# BEP2_rev1_seeed_55x88.net
KiCad netlist of a schematic drawn in EAGLE
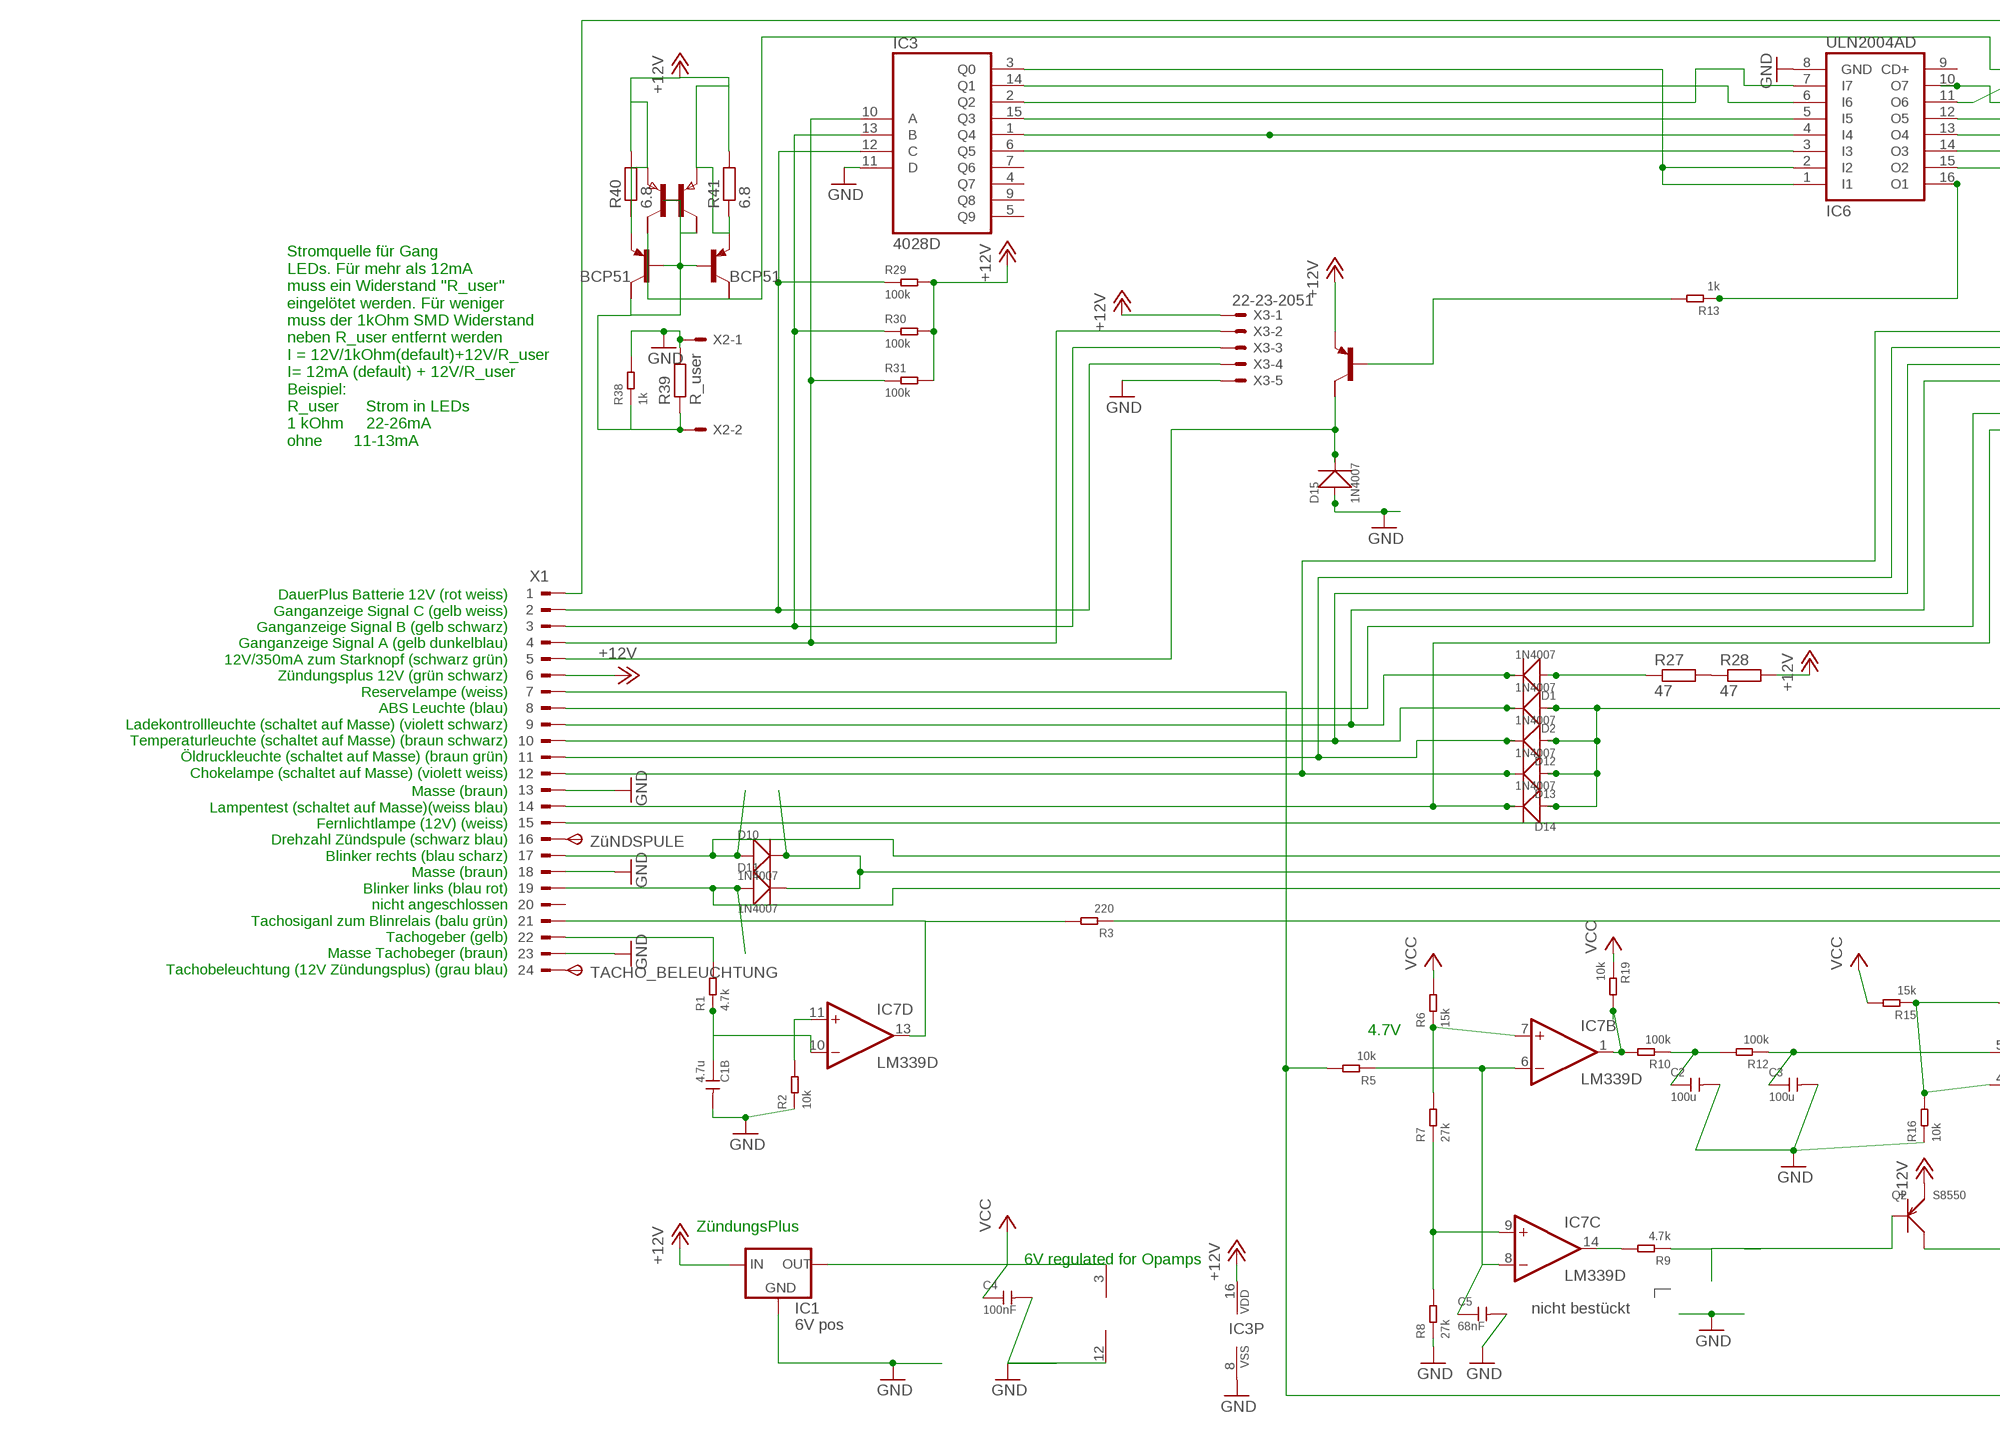
[diagram p0: schematic, sheet 1, part 1 of 2]
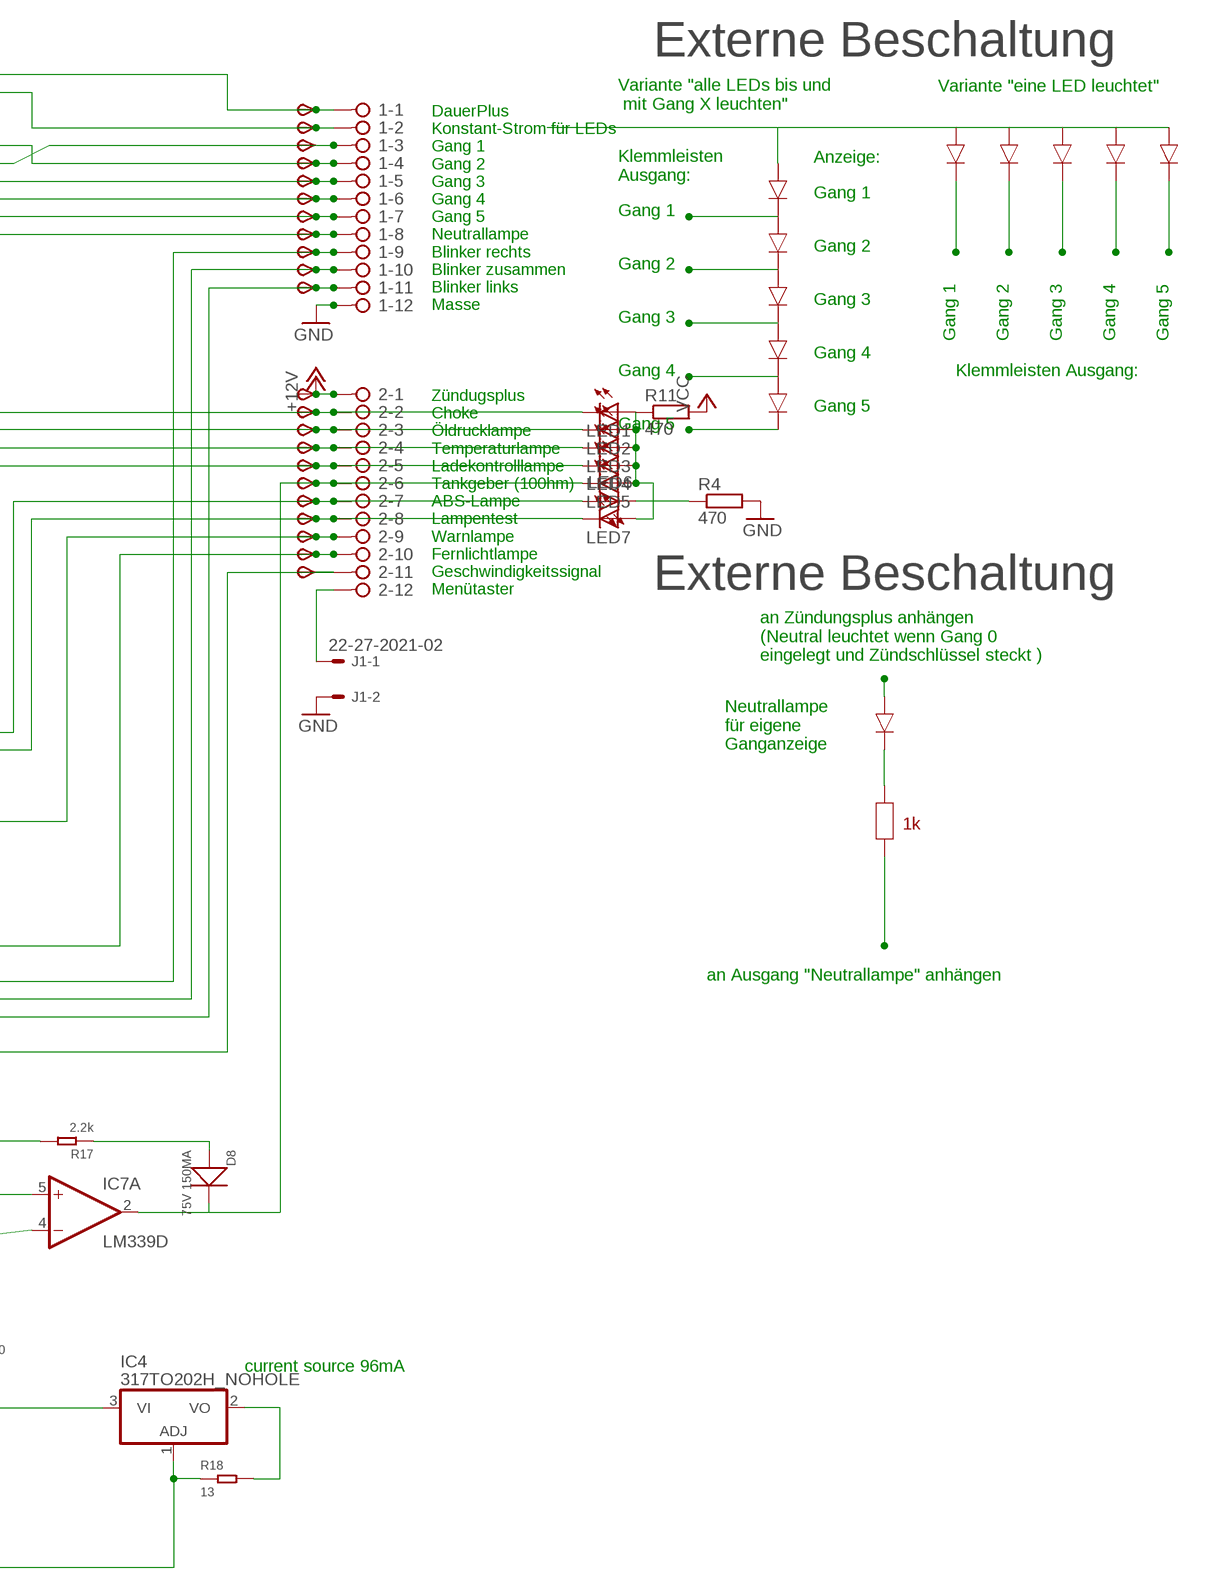
[diagram p1: schematic, sheet 1, part 2 of 2]

(export (version "E")
  (design (tool "Eeschema 10.0.6"))
  (components
    (comp (ref "1")
      (value "2081-1132")
      (footprint "eagle-import:12-PIN")
      (libsource (lib "eagle-import") (part "2081-1132"))
    )
    (comp (ref "2")
      (value "2081-1132")
      (footprint "eagle-import:12-PIN")
      (libsource (lib "eagle-import") (part "2081-1132"))
    )
    (comp (ref "C1B")
      (value "4.7u")
      (footprint "eagle-import:C0805")
      (fields (field (name "MPN") "CC0805KKX5R8BB475"))
      (libsource (lib "eagle-import") (part "CERAMIC-4.7UF-25V-10%-X5R(0805)"))
    )
    (comp (ref "C2")
      (value "100u")
      (footprint "eagle-import:C1206")
      (fields (field (name "MPN") "GRM31CR60J107ME39L"))
      (libsource (lib "eagle-import") (part "CERAMIC-100UF-6.3V-20%-X5R(1206)"))
    )
    (comp (ref "C3")
      (value "100u")
      (footprint "eagle-import:C1206")
      (fields (field (name "MPN") "GRM31CR60J107ME39L"))
      (libsource (lib "eagle-import") (part "CERAMIC-100UF-6.3V-20%-X5R(1206)"))
    )
    (comp (ref "C4")
      (value "100nF")
      (footprint "eagle-import:C0805")
      (fields (field (name "MPN") "CC0805KRX7R9BB104"))
      (libsource (lib "eagle-import") (part "CERAMIC-100NF-50V-10%-X7R(0805)"))
    )
    (comp (ref "C5")
      (value "68nF")
      (footprint "eagle-import:C0805")
      (fields (field (name "MPN") "CC0805KRX7R9BB104"))
      (libsource (lib "eagle-import") (part "CERAMIC-100NF-50V-10%-X7R(0805)"))
    )
    (comp (ref "D1")
      (value "1N4007")
      (footprint "eagle-import:DO-214AC")
      (libsource (lib "eagle-import") (part "DIODE-GEN-PURPOSE-1KV-1A(DO-214AC)"))
    )
    (comp (ref "D2")
      (value "1N4007")
      (footprint "eagle-import:DO-214AC")
      (libsource (lib "eagle-import") (part "DIODE-GEN-PURPOSE-1KV-1A(DO-214AC)"))
    )
    (comp (ref "D8")
      (value "75V 150MA")
      (footprint "eagle-import:LED-1206")
      (fields (field (name "MPN") "CD1206-S01575"))
      (libsource (lib "eagle-import") (part "SMD-DIODE-SWITCHING-75V-150MA(D1206)"))
    )
    (comp (ref "D10")
      (value "1N4007")
      (footprint "eagle-import:DO-214AC")
      (libsource (lib "eagle-import") (part "DIODE-GEN-PURPOSE-1KV-1A(DO-214AC)"))
    )
    (comp (ref "D11")
      (value "1N4007")
      (footprint "eagle-import:DO-214AC")
      (libsource (lib "eagle-import") (part "DIODE-GEN-PURPOSE-1KV-1A(DO-214AC)"))
    )
    (comp (ref "D12")
      (value "1N4007")
      (footprint "eagle-import:DO-214AC")
      (libsource (lib "eagle-import") (part "DIODE-GEN-PURPOSE-1KV-1A(DO-214AC)"))
    )
    (comp (ref "D13")
      (value "1N4007")
      (footprint "eagle-import:DO-214AC")
      (libsource (lib "eagle-import") (part "DIODE-GEN-PURPOSE-1KV-1A(DO-214AC)"))
    )
    (comp (ref "D14")
      (value "1N4007")
      (footprint "eagle-import:DO-214AC")
      (libsource (lib "eagle-import") (part "DIODE-GEN-PURPOSE-1KV-1A(DO-214AC)"))
    )
    (comp (ref "D15")
      (value "1N4007")
      (footprint "eagle-import:DO-214AC")
      (libsource (lib "eagle-import") (part "DIODE-GEN-PURPOSE-1KV-1A(DO-214AC)"))
    )
    (comp (ref "IC1")
      (value "6V pos")
      (footprint "eagle-import:78LXX")
      (libsource (lib "eagle-import") (part "78LXX"))
    )
    (comp (ref "IC3")
      (value "4028D")
      (footprint "eagle-import:SO16")
      (libsource (lib "eagle-import") (part "4028D"))
    )
    (comp (ref "IC4")
      (value "317TO202H_NOHOLE")
      (footprint "eagle-import:TO220H_NOHOLE")
      (libsource (lib "eagle-import") (part "317TO202H_NOHOLE"))
    )
    (comp (ref "IC6")
      (value "ULN2004AD")
      (footprint "eagle-import:SO16")
      (libsource (lib "eagle-import") (part "ULN2004AD"))
    )
    (comp (ref "IC7")
      (value "LM339D")
      (footprint "eagle-import:SO14")
      (libsource (lib "eagle-import") (part "LM339D"))
    )
    (comp (ref "J1")
      (value "22-27-2021-02")
      (footprint "eagle-import:6410-02")
      (libsource (lib "eagle-import") (part "22-?-0227-2021"))
    )
    (comp (ref "LED1")
      (value "LEDLD260")
      (footprint "eagle-import:LD260")
      (libsource (lib "eagle-import") (part "LEDLD260"))
    )
    (comp (ref "LED2")
      (value "LEDLD260")
      (footprint "eagle-import:LD260")
      (libsource (lib "eagle-import") (part "LEDLD260"))
    )
    (comp (ref "LED3")
      (value "LEDLD260")
      (footprint "eagle-import:LD260")
      (libsource (lib "eagle-import") (part "LEDLD260"))
    )
    (comp (ref "LED4")
      (value "LEDLD260")
      (footprint "eagle-import:LD260")
      (libsource (lib "eagle-import") (part "LEDLD260"))
    )
    (comp (ref "LED5")
      (value "LEDLD260")
      (footprint "eagle-import:LD260")
      (libsource (lib "eagle-import") (part "LEDLD260"))
    )
    (comp (ref "LED6")
      (value "LEDLD260")
      (footprint "eagle-import:LD260")
      (libsource (lib "eagle-import") (part "LEDLD260"))
    )
    (comp (ref "LED7")
      (value "LEDLD260")
      (footprint "eagle-import:LD260")
      (libsource (lib "eagle-import") (part "LEDLD260"))
    )
    (comp (ref "Q2")
      (value "S8550")
      (footprint "eagle-import:SOT-23")
      (libsource (lib "eagle-import") (part "SMD-TRANSISTORS-PNP-25V-500MA-S8550(SOT-23)"))
    )
    (comp (ref "Q3")
      (value "BCP53T1")
      (footprint "eagle-import:SOT223")
      (libsource (lib "eagle-import") (part "BCP53T1"))
    )
    (comp (ref "R1")
      (value "4.7k")
      (footprint "eagle-import:R0805")
      (fields (field (name "MPN") "RC0805JR-074K7L"))
      (libsource (lib "eagle-import") (part "SMD-RES-4.7K-5%-1/8W(0805)"))
    )
    (comp (ref "R2")
      (value "10k")
      (footprint "eagle-import:R0805")
      (fields (field (name "MPN") "RC0805FR-0710KL"))
      (libsource (lib "eagle-import") (part "SMD-RES-10K-1%-1/8W(0805)"))
    )
    (comp (ref "R3")
      (value "220")
      (footprint "eagle-import:R0805")
      (fields (field (name "MPN") "RC0805JR-07220RL"))
      (libsource (lib "eagle-import") (part "SMD-RES-220R-5%-1/8W(0805)"))
    )
    (comp (ref "R4")
      (value "470")
      (footprint "eagle-import:R0805")
      (libsource (lib "eagle-import") (part "R-EU_R0805"))
    )
    (comp (ref "R5")
      (value "10k")
      (footprint "eagle-import:R0805")
      (fields (field (name "MPN") "RC0805FR-0710KL"))
      (libsource (lib "eagle-import") (part "SMD-RES-10K-1%-1/8W(0805)"))
    )
    (comp (ref "R6")
      (value "15k")
      (footprint "eagle-import:R0805")
      (fields (field (name "MPN") "RC0805FR-0710KL"))
      (libsource (lib "eagle-import") (part "SMD-RES-10K-1%-1/8W(0805)"))
    )
    (comp (ref "R7")
      (value "27k")
      (footprint "eagle-import:R0603")
      (fields (field (name "MPN") "RC0603JR-0718KL"))
      (libsource (lib "eagle-import") (part "SMD-RES-18K-5%-1/10W(0603)"))
    )
    (comp (ref "R8")
      (value "27k")
      (footprint "eagle-import:R0603")
      (fields (field (name "MPN") "RC0603JR-0718KL"))
      (libsource (lib "eagle-import") (part "SMD-RES-18K-5%-1/10W(0603)"))
    )
    (comp (ref "R9")
      (value "4.7k")
      (footprint "eagle-import:R0805")
      (fields (field (name "MPN") "RC0805JR-074K7L"))
      (libsource (lib "eagle-import") (part "SMD-RES-4.7K-5%-1/8W(0805)"))
    )
    (comp (ref "R10")
      (value "100k")
      (footprint "eagle-import:R0603")
      (fields (field (name "MPN") "RC0603FR-07100KL"))
      (libsource (lib "eagle-import") (part "SMD-RES-100K-1%-1/10W(0603)"))
    )
    (comp (ref "R11")
      (value "470")
      (footprint "eagle-import:R0805")
      (libsource (lib "eagle-import") (part "R-EU_R0805"))
    )
    (comp (ref "R12")
      (value "100k")
      (footprint "eagle-import:R0603")
      (fields (field (name "MPN") "RC0603FR-07100KL"))
      (libsource (lib "eagle-import") (part "SMD-RES-100K-1%-1/10W(0603)"))
    )
    (comp (ref "R13")
      (value "1k")
      (footprint "eagle-import:R0805")
      (fields (field (name "MPN") "RC0805JR-071KL"))
      (libsource (lib "eagle-import") (part "SMD-RES-1K-5%-1/8W(0805)"))
    )
    (comp (ref "R15")
      (value "15k")
      (footprint "eagle-import:R0603")
      (fields (field (name "MPN") "RC0603FR-0715KL"))
      (libsource (lib "eagle-import") (part "SMD-RES-15K-1%-1/10W(0603)"))
    )
    (comp (ref "R16")
      (value "10k")
      (footprint "eagle-import:R0805")
      (fields (field (name "MPN") "RC0805FR-0710KL"))
      (libsource (lib "eagle-import") (part "SMD-RES-10K-1%-1/8W(0805)"))
    )
    (comp (ref "R17")
      (value "2.2k")
      (footprint "eagle-import:R0805")
      (fields (field (name "MPN") "RC0805JR-072K2L"))
      (libsource (lib "eagle-import") (part "SMD-RES-2.2K-5%-1/8W(0805)"))
    )
    (comp (ref "R18")
      (value "13")
      (footprint "eagle-import:R1206")
      (fields (field (name "MPN") "RC1206JR-0713RL"))
      (libsource (lib "eagle-import") (part "SMD-RES-13R-5%-1/4W(1206)"))
    )
    (comp (ref "R19")
      (value "10k")
      (footprint "eagle-import:R0805")
      (fields (field (name "MPN") "RC0805FR-0710KL"))
      (libsource (lib "eagle-import") (part "SMD-RES-10K-1%-1/8W(0805)"))
    )
    (comp (ref "R27")
      (value "47")
      (footprint "eagle-import:V235_17_1MM")
      (libsource (lib "eagle-import") (part "R-EU_V235/17_1MM"))
    )
    (comp (ref "R28")
      (value "47")
      (footprint "eagle-import:V235_17_1MM")
      (libsource (lib "eagle-import") (part "R-EU_V235/17_1MM"))
    )
    (comp (ref "R29")
      (value "100k")
      (footprint "eagle-import:R0603")
      (fields (field (name "MPN") "RC0603FR-07100KL"))
      (libsource (lib "eagle-import") (part "SMD-RES-100K-1%-1/10W(0603)"))
    )
    (comp (ref "R30")
      (value "100k")
      (footprint "eagle-import:R0603")
      (fields (field (name "MPN") "RC0603FR-07100KL"))
      (libsource (lib "eagle-import") (part "SMD-RES-100K-1%-1/10W(0603)"))
    )
    (comp (ref "R31")
      (value "100k")
      (footprint "eagle-import:R0603")
      (fields (field (name "MPN") "RC0603FR-07100KL"))
      (libsource (lib "eagle-import") (part "SMD-RES-100K-1%-1/10W(0603)"))
    )
    (comp (ref "R38")
      (value "1k")
      (footprint "eagle-import:R0805")
      (fields (field (name "MPN") "RC0805JR-071KL"))
      (libsource (lib "eagle-import") (part "SMD-RES-1K-5%-1/8W(0805)"))
    )
    (comp (ref "R39")
      (value "R_user")
      (footprint "eagle-import:R0805")
      (libsource (lib "eagle-import") (part "R-EU_R0805"))
    )
    (comp (ref "R40")
      (value "6.8")
      (footprint "eagle-import:R0805")
      (libsource (lib "eagle-import") (part "R-EU_R0805"))
    )
    (comp (ref "R41")
      (value "6.8")
      (footprint "eagle-import:R0805")
      (libsource (lib "eagle-import") (part "R-EU_R0805"))
    )
    (comp (ref "T1")
      (value "PNP2SM8")
      (footprint "eagle-import:SM8")
      (libsource (lib "eagle-import") (part "PNP2SM8"))
    )
    (comp (ref "T13")
      (value "BCP53T1")
      (footprint "eagle-import:SOT223")
      (fields (field (name "T") "BCP51"))
      (libsource (lib "eagle-import") (part "BCP53T1"))
    )
    (comp (ref "T14")
      (value "BCP53T1")
      (footprint "eagle-import:SOT223")
      (fields (field (name "T") "BCP51"))
      (libsource (lib "eagle-import") (part "BCP53T1"))
    )
    (comp (ref "TACHO_BELEUCHTUNG")
      (value "TPSP1_1MM")
      (footprint "eagle-import:P1_1.0MM")
      (libsource (lib "eagle-import") (part "TPSP1_1MM"))
    )
    (comp (ref "TP1")
      (value "TPSB1,27")
      (footprint "eagle-import:B1,27")
      (libsource (lib "eagle-import") (part "TPSB1,27"))
    )
    (comp (ref "TP2")
      (value "TPSB1,27")
      (footprint "eagle-import:B1,27")
      (libsource (lib "eagle-import") (part "TPSB1,27"))
    )
    (comp (ref "TP3")
      (value "TPSB1,27")
      (footprint "eagle-import:B1,27")
      (libsource (lib "eagle-import") (part "TPSB1,27"))
    )
    (comp (ref "TP4")
      (value "TPSB1,27")
      (footprint "eagle-import:B1,27")
      (libsource (lib "eagle-import") (part "TPSB1,27"))
    )
    (comp (ref "TP5")
      (value "TPSB1,27")
      (footprint "eagle-import:B1,27")
      (libsource (lib "eagle-import") (part "TPSB1,27"))
    )
    (comp (ref "TP6")
      (value "TPSB1,27")
      (footprint "eagle-import:B1,27")
      (libsource (lib "eagle-import") (part "TPSB1,27"))
    )
    (comp (ref "TP7")
      (value "TPSB1,27")
      (footprint "eagle-import:B1,27")
      (libsource (lib "eagle-import") (part "TPSB1,27"))
    )
    (comp (ref "TP8")
      (value "TPSB1,27")
      (footprint "eagle-import:B1,27")
      (libsource (lib "eagle-import") (part "TPSB1,27"))
    )
    (comp (ref "TP9")
      (value "TPSB1,27")
      (footprint "eagle-import:B1,27")
      (libsource (lib "eagle-import") (part "TPSB1,27"))
    )
    (comp (ref "TP10")
      (value "TPSB1,27")
      (footprint "eagle-import:B1,27")
      (libsource (lib "eagle-import") (part "TPSB1,27"))
    )
    (comp (ref "TP11")
      (value "TPSB1,27")
      (footprint "eagle-import:B1,27")
      (libsource (lib "eagle-import") (part "TPSB1,27"))
    )
    (comp (ref "TP12")
      (value "TPSB1,27")
      (footprint "eagle-import:B1,27")
      (libsource (lib "eagle-import") (part "TPSB1,27"))
    )
    (comp (ref "TP16")
      (value "TPSB1,27")
      (footprint "eagle-import:B1,27")
      (libsource (lib "eagle-import") (part "TPSB1,27"))
    )
    (comp (ref "TP17")
      (value "TPSB1,27")
      (footprint "eagle-import:B1,27")
      (libsource (lib "eagle-import") (part "TPSB1,27"))
    )
    (comp (ref "TP18")
      (value "TPSB1,27")
      (footprint "eagle-import:B1,27")
      (libsource (lib "eagle-import") (part "TPSB1,27"))
    )
    (comp (ref "TP19")
      (value "TPSB1,27")
      (footprint "eagle-import:B1,27")
      (libsource (lib "eagle-import") (part "TPSB1,27"))
    )
    (comp (ref "TP21")
      (value "TPSB1,27")
      (footprint "eagle-import:B1,27")
      (libsource (lib "eagle-import") (part "TPSB1,27"))
    )
    (comp (ref "TP22")
      (value "TPSB1,27")
      (footprint "eagle-import:B1,27")
      (libsource (lib "eagle-import") (part "TPSB1,27"))
    )
    (comp (ref "TP23")
      (value "TPSB1,27")
      (footprint "eagle-import:B1,27")
      (libsource (lib "eagle-import") (part "TPSB1,27"))
    )
    (comp (ref "TP24")
      (value "TPSB1,27")
      (footprint "eagle-import:B1,27")
      (libsource (lib "eagle-import") (part "TPSB1,27"))
    )
    (comp (ref "TP25")
      (value "TPSB1,27")
      (footprint "eagle-import:B1,27")
      (libsource (lib "eagle-import") (part "TPSB1,27"))
    )
    (comp (ref "TP26")
      (value "TPSB1,27")
      (footprint "eagle-import:B1,27")
      (libsource (lib "eagle-import") (part "TPSB1,27"))
    )
    (comp (ref "X1")
      (value "CON_BMW")
      (footprint "eagle-import:24-PIN")
      (libsource (lib "eagle-import") (part "CON_BMW"))
    )
    (comp (ref "X2")
      (value "22-23-2021")
      (footprint "eagle-import:22-23-2021")
      (fields (field (name "MF") "MOLEX"))
      (libsource (lib "eagle-import") (part "22-23-2021"))
    )
    (comp (ref "X3")
      (value "22-23-2051")
      (footprint "eagle-import:22-23-2051")
      (fields (field (name "MF") "MOLEX"))
      (libsource (lib "eagle-import") (part "22-23-2051"))
    )
    (comp (ref "ZüNDSPULE")
      (value "TPSP1_1MM")
      (footprint "eagle-import:P1_1.0MM")
      (libsource (lib "eagle-import") (part "TPSP1_1MM"))
    )
  )
  (nets
    (net (code "1") (name "+12V") (class "Default")
      (node (ref "2") (pin "1") (pinfunction "KL_1") (pintype "passive"))
      (node (ref "IC1") (pin "IN") (pinfunction "IN_IN") (pintype "input"))
      (node (ref "IC3") (pin "16") (pinfunction "VDD_16") (pintype "power_in"))
      (node (ref "Q2") (pin "2") (pinfunction "E_2") (pintype "passive"))
      (node (ref "Q3") (pin "3") (pinfunction "E_3") (pintype "passive"))
      (node (ref "R28") (pin "2") (pinfunction "2_2") (pintype "passive"))
      (node (ref "R29") (pin "2") (pinfunction "2_2") (pintype "passive"))
      (node (ref "R30") (pin "2") (pinfunction "2_2") (pintype "passive"))
      (node (ref "R31") (pin "2") (pinfunction "2_2") (pintype "passive"))
      (node (ref "R40") (pin "1") (pinfunction "1_1") (pintype "passive"))
      (node (ref "R40") (pin "2") (pinfunction "2_2") (pintype "passive"))
      (node (ref "R41") (pin "1") (pinfunction "1_1") (pintype "passive"))
      (node (ref "R41") (pin "2") (pinfunction "2_2") (pintype "passive"))
      (node (ref "T1") (pin "1") (pinfunction "E_1") (pintype "passive"))
      (node (ref "T1") (pin "3") (pinfunction "E_3") (pintype "passive"))
      (node (ref "T13") (pin "3") (pinfunction "E_3") (pintype "passive"))
      (node (ref "T14") (pin "3") (pinfunction "E_3") (pintype "passive"))
      (node (ref "TP12") (pin "TP") (pinfunction "PP_TP") (pintype "input"))
      (node (ref "X1") (pin "6") (pinfunction "6_6") (pintype "passive"))
      (node (ref "X3") (pin "1") (pinfunction "S_1") (pintype "passive"))
    )
    (net (code "2") (name "GND") (class "Default")
      (node (ref "1") (pin "12") (pinfunction "KL_12") (pintype "passive"))
      (node (ref "C1B") (pin "2") (pinfunction "2_2") (pintype "passive"))
      (node (ref "C2") (pin "2") (pinfunction "2_2") (pintype "passive"))
      (node (ref "C3") (pin "2") (pinfunction "2_2") (pintype "passive"))
      (node (ref "C4") (pin "2") (pinfunction "2_2") (pintype "passive"))
      (node (ref "C5") (pin "2") (pinfunction "2_2") (pintype "passive"))
      (node (ref "D15") (pin "1") (pinfunction "+_1") (pintype "passive"))
      (node (ref "IC1") (pin "GND") (pinfunction "GND_GND") (pintype "input"))
      (node (ref "IC3") (pin "11") (pinfunction "D_11") (pintype "input"))
      (node (ref "IC3") (pin "8") (pinfunction "VSS_8") (pintype "power_in"))
      (node (ref "IC6") (pin "8") (pinfunction "GND_8") (pintype "power_in"))
      (node (ref "IC7") (pin "12") (pinfunction "GND_12") (pintype "power_in"))
      (node (ref "J1") (pin "2") (pinfunction "S_2") (pintype "passive"))
      (node (ref "R16") (pin "1") (pinfunction "1_1") (pintype "passive"))
      (node (ref "R2") (pin "1") (pinfunction "1_1") (pintype "passive"))
      (node (ref "R38") (pin "2") (pinfunction "2_2") (pintype "passive"))
      (node (ref "R39") (pin "2") (pinfunction "2_2") (pintype "passive"))
      (node (ref "R4") (pin "2") (pinfunction "2_2") (pintype "passive"))
      (node (ref "R8") (pin "1") (pinfunction "1_1") (pintype "passive"))
      (node (ref "X1") (pin "13") (pinfunction "13_13") (pintype "passive"))
      (node (ref "X1") (pin "18") (pinfunction "18_18") (pintype "passive"))
      (node (ref "X1") (pin "23") (pinfunction "23_23") (pintype "passive"))
      (node (ref "X2") (pin "1") (pinfunction "S_1") (pintype "passive"))
      (node (ref "X3") (pin "5") (pinfunction "S_5") (pintype "passive"))
    )
    (net (code "3") (name "Net-(1A-KL)") (class "Default")
      (node (ref "1") (pin "1") (pinfunction "KL_1") (pintype "passive"))
      (node (ref "TP1") (pin "TP") (pinfunction "PP_TP") (pintype "input"))
      (node (ref "X1") (pin "1") (pinfunction "1_1") (pintype "passive"))
    )
    (net (code "4") (name "Net-(1B-KL)") (class "Default")
      (node (ref "1") (pin "10") (pinfunction "KL_10") (pintype "passive"))
      (node (ref "D10") (pin "2") (pinfunction "-_2") (pintype "passive"))
      (node (ref "D11") (pin "2") (pinfunction "-_2") (pintype "passive"))
      (node (ref "TP10") (pin "TP") (pinfunction "PP_TP") (pintype "input"))
    )
    (net (code "5") (name "Net-(1C-KL)") (class "Default")
      (node (ref "1") (pin "11") (pinfunction "KL_11") (pintype "passive"))
      (node (ref "D11") (pin "1") (pinfunction "+_1") (pintype "passive"))
      (node (ref "TP11") (pin "TP") (pinfunction "PP_TP") (pintype "input"))
      (node (ref "X1") (pin "19") (pinfunction "19_19") (pintype "passive"))
    )
    (net (code "6") (name "Net-(1E-KL)") (class "Default")
      (node (ref "1") (pin "2") (pinfunction "KL_2") (pintype "passive"))
      (node (ref "T1") (pin "8") (pinfunction "C1_8") (pintype "passive"))
      (node (ref "T14") (pin "2") (pinfunction "C_2") (pintype "passive"))
      (node (ref "TP2") (pin "TP") (pinfunction "PP_TP") (pintype "input"))
    )
    (net (code "7") (name "Net-(1F-KL)") (class "Default")
      (node (ref "1") (pin "3") (pinfunction "KL_3") (pintype "passive"))
      (node (ref "IC6") (pin "11") (pinfunction "O6_11") (pintype "open_collector"))
      (node (ref "TP3") (pin "TP") (pinfunction "PP_TP") (pintype "input"))
    )
    (net (code "8") (name "Net-(1G-KL)") (class "Default")
      (node (ref "1") (pin "4") (pinfunction "KL_4") (pintype "passive"))
      (node (ref "IC6") (pin "10") (pinfunction "O7_10") (pintype "open_collector"))
      (node (ref "TP4") (pin "TP") (pinfunction "PP_TP") (pintype "input"))
    )
    (net (code "9") (name "Net-(1H-KL)") (class "Default")
      (node (ref "1") (pin "5") (pinfunction "KL_5") (pintype "passive"))
      (node (ref "IC6") (pin "12") (pinfunction "O5_12") (pintype "open_collector"))
      (node (ref "TP5") (pin "TP") (pinfunction "PP_TP") (pintype "input"))
    )
    (net (code "10") (name "Net-(1I-KL)") (class "Default")
      (node (ref "1") (pin "6") (pinfunction "KL_6") (pintype "passive"))
      (node (ref "IC6") (pin "13") (pinfunction "O4_13") (pintype "open_collector"))
      (node (ref "TP6") (pin "TP") (pinfunction "PP_TP") (pintype "input"))
    )
    (net (code "11") (name "Net-(1J-KL)") (class "Default")
      (node (ref "1") (pin "7") (pinfunction "KL_7") (pintype "passive"))
      (node (ref "IC6") (pin "14") (pinfunction "O3_14") (pintype "open_collector"))
      (node (ref "TP7") (pin "TP") (pinfunction "PP_TP") (pintype "input"))
    )
    (net (code "12") (name "Net-(1K-KL)") (class "Default")
      (node (ref "1") (pin "8") (pinfunction "KL_8") (pintype "passive"))
      (node (ref "IC6") (pin "15") (pinfunction "O2_15") (pintype "open_collector"))
      (node (ref "TP8") (pin "TP") (pinfunction "PP_TP") (pintype "input"))
    )
    (net (code "13") (name "Net-(1L-KL)") (class "Default")
      (node (ref "1") (pin "9") (pinfunction "KL_9") (pintype "passive"))
      (node (ref "D10") (pin "1") (pinfunction "+_1") (pintype "passive"))
      (node (ref "TP9") (pin "TP") (pinfunction "PP_TP") (pintype "input"))
      (node (ref "X1") (pin "17") (pinfunction "17_17") (pintype "passive"))
    )
    (net (code "14") (name "Net-(2B-KL)") (class "Default")
      (node (ref "2") (pin "10") (pinfunction "KL_10") (pintype "passive"))
      (node (ref "TP25") (pin "TP") (pinfunction "PP_TP") (pintype "input"))
      (node (ref "X1") (pin "15") (pinfunction "15_15") (pintype "passive"))
    )
    (net (code "15") (name "Net-(2C-KL)") (class "Default")
      (node (ref "2") (pin "11") (pinfunction "KL_11") (pintype "passive"))
      (node (ref "R3") (pin "1") (pinfunction "1_1") (pintype "passive"))
      (node (ref "TP26") (pin "TP") (pinfunction "PP_TP") (pintype "input"))
    )
    (net (code "16") (name "Net-(2D-KL)") (class "Default")
      (node (ref "2") (pin "12") (pinfunction "KL_12") (pintype "passive"))
      (node (ref "J1") (pin "1") (pinfunction "S_1") (pintype "passive"))
    )
    (net (code "17") (name "Net-(2E-KL)") (class "Default")
      (node (ref "2") (pin "2") (pinfunction "KL_2") (pintype "passive"))
      (node (ref "D13") (pin "2") (pinfunction "-_2") (pintype "passive"))
      (node (ref "LED1") (pin "K") (pinfunction "C_K") (pintype "passive"))
      (node (ref "TP16") (pin "TP") (pinfunction "PP_TP") (pintype "input"))
      (node (ref "X1") (pin "12") (pinfunction "12_12") (pintype "passive"))
    )
    (net (code "18") (name "Net-(2F-KL)") (class "Default")
      (node (ref "2") (pin "3") (pinfunction "KL_3") (pintype "passive"))
      (node (ref "D12") (pin "2") (pinfunction "-_2") (pintype "passive"))
      (node (ref "LED2") (pin "K") (pinfunction "C_K") (pintype "passive"))
      (node (ref "TP17") (pin "TP") (pinfunction "PP_TP") (pintype "input"))
      (node (ref "X1") (pin "11") (pinfunction "11_11") (pintype "passive"))
    )
    (net (code "19") (name "Net-(2G-KL)") (class "Default")
      (node (ref "2") (pin "4") (pinfunction "KL_4") (pintype "passive"))
      (node (ref "D2") (pin "2") (pinfunction "-_2") (pintype "passive"))
      (node (ref "LED3") (pin "K") (pinfunction "C_K") (pintype "passive"))
      (node (ref "TP18") (pin "TP") (pinfunction "PP_TP") (pintype "input"))
      (node (ref "X1") (pin "10") (pinfunction "10_10") (pintype "passive"))
    )
    (net (code "20") (name "Net-(2H-KL)") (class "Default")
      (node (ref "2") (pin "5") (pinfunction "KL_5") (pintype "passive"))
      (node (ref "D1") (pin "2") (pinfunction "-_2") (pintype "passive"))
      (node (ref "LED4") (pin "K") (pinfunction "C_K") (pintype "passive"))
      (node (ref "TP19") (pin "TP") (pinfunction "PP_TP") (pintype "input"))
      (node (ref "X1") (pin "9") (pinfunction "9_9") (pintype "passive"))
    )
    (net (code "21") (name "Net-(2I-KL)") (class "Default")
      (node (ref "2") (pin "6") (pinfunction "KL_6") (pintype "passive"))
      (node (ref "D8") (pin "-") (pinfunction "-_-") (pintype "passive"))
      (node (ref "IC7") (pin "2") (pinfunction "OUT_2") (pintype "open_collector"))
      (node (ref "LED5") (pin "K") (pinfunction "C_K") (pintype "passive"))
      (node (ref "TP21") (pin "TP") (pinfunction "PP_TP") (pintype "input"))
    )
    (net (code "22") (name "Net-(2J-KL)") (class "Default")
      (node (ref "2") (pin "7") (pinfunction "KL_7") (pintype "passive"))
      (node (ref "LED6") (pin "A") (pinfunction "A_A") (pintype "passive"))
      (node (ref "TP22") (pin "TP") (pinfunction "PP_TP") (pintype "input"))
      (node (ref "X1") (pin "8") (pinfunction "8_8") (pintype "passive"))
    )
    (net (code "23") (name "Net-(2K-KL)") (class "Default")
      (node (ref "2") (pin "8") (pinfunction "KL_8") (pintype "passive"))
      (node (ref "D14") (pin "2") (pinfunction "-_2") (pintype "passive"))
      (node (ref "LED7") (pin "K") (pinfunction "C_K") (pintype "passive"))
      (node (ref "TP23") (pin "TP") (pinfunction "PP_TP") (pintype "input"))
      (node (ref "X1") (pin "14") (pinfunction "14_14") (pintype "passive"))
    )
    (net (code "24") (name "Net-(2L-KL)") (class "Default")
      (node (ref "2") (pin "9") (pinfunction "KL_9") (pintype "passive"))
      (node (ref "D12") (pin "1") (pinfunction "+_1") (pintype "passive"))
      (node (ref "D13") (pin "1") (pinfunction "+_1") (pintype "passive"))
      (node (ref "D14") (pin "1") (pinfunction "+_1") (pintype "passive"))
      (node (ref "D2") (pin "1") (pinfunction "+_1") (pintype "passive"))
      (node (ref "TP24") (pin "TP") (pinfunction "PP_TP") (pintype "input"))
    )
    (net (code "25") (name "Net-(C2-Pad1)") (class "Default")
      (node (ref "C2") (pin "1") (pinfunction "1_1") (pintype "passive"))
      (node (ref "R10") (pin "1") (pinfunction "1_1") (pintype "passive"))
      (node (ref "R12") (pin "2") (pinfunction "2_2") (pintype "passive"))
    )
    (net (code "26") (name "Net-(D1-+)") (class "Default")
      (node (ref "D1") (pin "1") (pinfunction "+_1") (pintype "passive"))
      (node (ref "R27") (pin "1") (pinfunction "1_1") (pintype "passive"))
    )
    (net (code "27") (name "Net-(D8-Pad+)") (class "Default")
      (node (ref "D8") (pin "+") (pinfunction "+_+") (pintype "passive"))
      (node (ref "R17") (pin "1") (pinfunction "1_1") (pintype "passive"))
    )
    (net (code "28") (name "Net-(D15--)") (class "Default")
      (node (ref "D15") (pin "2") (pinfunction "-_2") (pintype "passive"))
      (node (ref "Q3") (pin "2") (pinfunction "C_2") (pintype "passive"))
      (node (ref "X1") (pin "5") (pinfunction "5_5") (pintype "passive"))
    )
    (net (code "29") (name "Net-(IC3A-A)") (class "Default")
      (node (ref "IC3") (pin "10") (pinfunction "A_10") (pintype "input"))
      (node (ref "R31") (pin "1") (pinfunction "1_1") (pintype "passive"))
      (node (ref "X1") (pin "4") (pinfunction "4_4") (pintype "passive"))
      (node (ref "X3") (pin "2") (pinfunction "S_2") (pintype "passive"))
    )
    (net (code "30") (name "Net-(IC3A-B)") (class "Default")
      (node (ref "IC3") (pin "13") (pinfunction "B_13") (pintype "input"))
      (node (ref "R30") (pin "1") (pinfunction "1_1") (pintype "passive"))
      (node (ref "X1") (pin "3") (pinfunction "3_3") (pintype "passive"))
      (node (ref "X3") (pin "3") (pinfunction "S_3") (pintype "passive"))
    )
    (net (code "31") (name "Net-(IC3A-C)") (class "Default")
      (node (ref "IC3") (pin "12") (pinfunction "C_12") (pintype "input"))
      (node (ref "R29") (pin "1") (pinfunction "1_1") (pintype "passive"))
      (node (ref "X1") (pin "2") (pinfunction "2_2") (pintype "passive"))
      (node (ref "X3") (pin "4") (pinfunction "S_4") (pintype "passive"))
    )
    (net (code "32") (name "Net-(IC3A-Q0)") (class "Default")
      (node (ref "IC3") (pin "3") (pinfunction "Q0_3") (pintype "output"))
      (node (ref "IC6") (pin "1") (pinfunction "I1_1") (pintype "input"))
      (node (ref "IC6") (pin "2") (pinfunction "I2_2") (pintype "input"))
    )
    (net (code "33") (name "Net-(IC3A-Q1)") (class "Default")
      (node (ref "IC3") (pin "14") (pinfunction "Q1_14") (pintype "output"))
      (node (ref "IC6") (pin "6") (pinfunction "I6_6") (pintype "input"))
    )
    (net (code "34") (name "Net-(IC3A-Q2)") (class "Default")
      (node (ref "IC3") (pin "2") (pinfunction "Q2_2") (pintype "output"))
      (node (ref "IC6") (pin "7") (pinfunction "I7_7") (pintype "input"))
    )
    (net (code "35") (name "Net-(IC3A-Q3)") (class "Default")
      (node (ref "IC3") (pin "15") (pinfunction "Q3_15") (pintype "output"))
      (node (ref "IC6") (pin "5") (pinfunction "I5_5") (pintype "input"))
    )
    (net (code "36") (name "Net-(IC3A-Q4)") (class "Default")
      (node (ref "IC3") (pin "1") (pinfunction "Q4_1") (pintype "output"))
      (node (ref "IC6") (pin "4") (pinfunction "I4_4") (pintype "input"))
    )
    (net (code "37") (name "Net-(IC3A-Q5)") (class "Default")
      (node (ref "IC3") (pin "6") (pinfunction "Q5_6") (pintype "output"))
      (node (ref "IC6") (pin "3") (pinfunction "I3_3") (pintype "input"))
    )
    (net (code "38") (name "Net-(IC4-ADJ)") (class "Default")
      (node (ref "IC4") (pin "1") (pinfunction "ADJ_1") (pintype "input"))
      (node (ref "R18") (pin "1") (pinfunction "1_1") (pintype "passive"))
      (node (ref "R5") (pin "2") (pinfunction "2_2") (pintype "passive"))
      (node (ref "X1") (pin "7") (pinfunction "7_7") (pintype "passive"))
    )
    (net (code "39") (name "Net-(IC4-VI)") (class "Default")
      (node (ref "IC4") (pin "3") (pinfunction "VI_3") (pintype "input"))
      (node (ref "Q2") (pin "3") (pinfunction "C_3") (pintype "passive"))
    )
    (net (code "40") (name "Net-(IC4-VO)") (class "Default")
      (node (ref "IC4") (pin "2") (pinfunction "VO_2") (pintype "passive"))
      (node (ref "R18") (pin "2") (pinfunction "2_2") (pintype "passive"))
    )
    (net (code "41") (name "Net-(IC6-O1)") (class "Default")
      (node (ref "IC6") (pin "16") (pinfunction "O1_16") (pintype "open_collector"))
      (node (ref "R13") (pin "1") (pinfunction "1_1") (pintype "passive"))
    )
    (net (code "42") (name "Net-(IC7A-+IN)") (class "Default")
      (node (ref "C3") (pin "1") (pinfunction "1_1") (pintype "passive"))
      (node (ref "IC7") (pin "5") (pinfunction "+IN_5") (pintype "input"))
      (node (ref "R12") (pin "1") (pinfunction "1_1") (pintype "passive"))
    )
    (net (code "43") (name "Net-(IC7A--IN)") (class "Default")
      (node (ref "IC7") (pin "4") (pinfunction "-IN_4") (pintype "input"))
      (node (ref "R15") (pin "1") (pinfunction "1_1") (pintype "passive"))
      (node (ref "R16") (pin "2") (pinfunction "2_2") (pintype "passive"))
      (node (ref "R17") (pin "2") (pinfunction "2_2") (pintype "passive"))
    )
    (net (code "44") (name "Net-(IC7B-+IN)") (class "Default")
      (node (ref "IC7") (pin "7") (pinfunction "+IN_7") (pintype "input"))
      (node (ref "R6") (pin "1") (pinfunction "1_1") (pintype "passive"))
      (node (ref "R7") (pin "2") (pinfunction "2_2") (pintype "passive"))
    )
    (net (code "45") (name "Net-(IC7B--IN)") (class "Default")
      (node (ref "C5") (pin "1") (pinfunction "1_1") (pintype "passive"))
      (node (ref "IC7") (pin "6") (pinfunction "-IN_6") (pintype "input"))
      (node (ref "IC7") (pin "8") (pinfunction "-IN_8") (pintype "input"))
      (node (ref "R5") (pin "1") (pinfunction "1_1") (pintype "passive"))
    )
    (net (code "46") (name "Net-(IC7B-OUT)") (class "Default")
      (node (ref "IC7") (pin "1") (pinfunction "OUT_1") (pintype "open_collector"))
      (node (ref "R10") (pin "2") (pinfunction "2_2") (pintype "passive"))
      (node (ref "R19") (pin "2") (pinfunction "2_2") (pintype "passive"))
    )
    (net (code "47") (name "Net-(IC7C-+IN)") (class "Default")
      (node (ref "IC7") (pin "9") (pinfunction "+IN_9") (pintype "input"))
      (node (ref "R7") (pin "1") (pinfunction "1_1") (pintype "passive"))
      (node (ref "R8") (pin "2") (pinfunction "2_2") (pintype "passive"))
    )
    (net (code "48") (name "Net-(IC7C-OUT)") (class "Default")
      (node (ref "IC7") (pin "14") (pinfunction "OUT_14") (pintype "open_collector"))
      (node (ref "R9") (pin "2") (pinfunction "2_2") (pintype "passive"))
    )
    (net (code "49") (name "Net-(IC7D-+IN)") (class "Default")
      (node (ref "IC7") (pin "11") (pinfunction "+IN_11") (pintype "input"))
      (node (ref "R2") (pin "2") (pinfunction "2_2") (pintype "passive"))
    )
    (net (code "50") (name "Net-(IC7D--IN)") (class "Default")
      (node (ref "C1B") (pin "1") (pinfunction "1_1") (pintype "passive"))
      (node (ref "IC7") (pin "10") (pinfunction "-IN_10") (pintype "input"))
      (node (ref "R1") (pin "1") (pinfunction "1_1") (pintype "passive"))
    )
    (net (code "51") (name "Net-(IC7D-OUT)") (class "Default")
      (node (ref "IC7") (pin "13") (pinfunction "OUT_13") (pintype "open_collector"))
      (node (ref "R3") (pin "2") (pinfunction "2_2") (pintype "passive"))
      (node (ref "X1") (pin "21") (pinfunction "21_21") (pintype "passive"))
    )
    (net (code "52") (name "Net-(LED1-PadA)") (class "Default")
      (node (ref "LED1") (pin "A") (pinfunction "A_A") (pintype "passive"))
      (node (ref "LED2") (pin "A") (pinfunction "A_A") (pintype "passive"))
      (node (ref "LED3") (pin "A") (pinfunction "A_A") (pintype "passive"))
      (node (ref "LED4") (pin "A") (pinfunction "A_A") (pintype "passive"))
      (node (ref "LED5") (pin "A") (pinfunction "A_A") (pintype "passive"))
      (node (ref "LED7") (pin "A") (pinfunction "A_A") (pintype "passive"))
      (node (ref "R11") (pin "1") (pinfunction "1_1") (pintype "passive"))
    )
    (net (code "53") (name "Net-(LED6-C)") (class "Default")
      (node (ref "LED6") (pin "K") (pinfunction "C_K") (pintype "passive"))
      (node (ref "R4") (pin "1") (pinfunction "1_1") (pintype "passive"))
    )
    (net (code "54") (name "Net-(Q2-B)") (class "Default")
      (node (ref "Q2") (pin "1") (pinfunction "B_1") (pintype "passive"))
      (node (ref "R9") (pin "1") (pinfunction "1_1") (pintype "passive"))
    )
    (net (code "55") (name "Net-(Q3-B)") (class "Default")
      (node (ref "Q3") (pin "1") (pinfunction "B_1") (pintype "passive"))
      (node (ref "R13") (pin "2") (pinfunction "2_2") (pintype "passive"))
    )
    (net (code "56") (name "Net-(R1-Pad2)") (class "Default")
      (node (ref "R1") (pin "2") (pinfunction "2_2") (pintype "passive"))
      (node (ref "X1") (pin "22") (pinfunction "22_22") (pintype "passive"))
    )
    (net (code "57") (name "Net-(R27-Pad2)") (class "Default")
      (node (ref "R27") (pin "2") (pinfunction "2_2") (pintype "passive"))
      (node (ref "R28") (pin "1") (pinfunction "1_1") (pintype "passive"))
    )
    (net (code "58") (name "Net-(T13-B)") (class "Default")
      (node (ref "R38") (pin "1") (pinfunction "1_1") (pintype "passive"))
      (node (ref "R39") (pin "1") (pinfunction "1_1") (pintype "passive"))
      (node (ref "T1") (pin "2") (pinfunction "B_2") (pintype "passive"))
      (node (ref "T1") (pin "4") (pinfunction "B_4") (pintype "passive"))
      (node (ref "T1") (pin "6") (pinfunction "C1_6") (pintype "passive"))
      (node (ref "T13") (pin "1") (pinfunction "B_1") (pintype "passive"))
      (node (ref "T13") (pin "2") (pinfunction "C_2") (pintype "passive"))
      (node (ref "T14") (pin "1") (pinfunction "B_1") (pintype "passive"))
      (node (ref "X2") (pin "2") (pinfunction "S_2") (pintype "passive"))
    )
    (net (code "59") (name "Net-(TACHO_BELEUCHTUNG-PP)") (class "Default")
      (node (ref "TACHO_BELEUCHTUNG") (pin "TP") (pinfunction "PP_TP") (pintype "input"))
      (node (ref "X1") (pin "24") (pinfunction "24_24") (pintype "passive"))
    )
    (net (code "60") (name "Net-(ZüNDSPULE-PP)") (class "Default")
      (node (ref "X1") (pin "16") (pinfunction "16_16") (pintype "passive"))
      (node (ref "ZüNDSPULE") (pin "TP") (pinfunction "PP_TP") (pintype "input"))
    )
    (net (code "61") (name "VCC") (class "Default")
      (node (ref "C4") (pin "1") (pinfunction "1_1") (pintype "passive"))
      (node (ref "IC1") (pin "OUT") (pinfunction "OUT_OUT") (pintype "passive"))
      (node (ref "IC7") (pin "3") (pinfunction "V+_3") (pintype "power_in"))
      (node (ref "R11") (pin "2") (pinfunction "2_2") (pintype "passive"))
      (node (ref "R15") (pin "2") (pinfunction "2_2") (pintype "passive"))
      (node (ref "R19") (pin "1") (pinfunction "1_1") (pintype "passive"))
      (node (ref "R6") (pin "2") (pinfunction "2_2") (pintype "passive"))
    )
    (net (code "62") (name "unconnected-(IC3A-Q6-Pad7)") (class "Default")
      (node (ref "IC3") (pin "7") (pinfunction "Q6_7") (pintype "output"))
    )
    (net (code "63") (name "unconnected-(IC3A-Q7-Pad4)") (class "Default")
      (node (ref "IC3") (pin "4") (pinfunction "Q7_4") (pintype "output"))
    )
    (net (code "64") (name "unconnected-(IC3A-Q8-Pad9)") (class "Default")
      (node (ref "IC3") (pin "9") (pinfunction "Q8_9") (pintype "output"))
    )
    (net (code "65") (name "unconnected-(IC3A-Q9-Pad5)") (class "Default")
      (node (ref "IC3") (pin "5") (pinfunction "Q9_5") (pintype "output"))
    )
    (net (code "66") (name "unconnected-(IC6-CD+-Pad9)") (class "Default")
      (node (ref "IC6") (pin "9") (pinfunction "CD+_9") (pintype "passive"))
    )
    (net (code "67") (name "unconnected-(Q3-C{slash}-Pad4)") (class "Default")
      (node (ref "Q3") (pin "4") (pinfunction "C/_4") (pintype "passive"))
    )
    (net (code "68") (name "unconnected-(T1A-C-Pad5)") (class "Default")
      (node (ref "T1") (pin "5") (pinfunction "C_5") (pintype "passive"))
    )
    (net (code "69") (name "unconnected-(T1B-C-Pad7)") (class "Default")
      (node (ref "T1") (pin "7") (pinfunction "C_7") (pintype "passive"))
    )
    (net (code "70") (name "unconnected-(T13-C{slash}-Pad4)") (class "Default")
      (node (ref "T13") (pin "4") (pinfunction "C/_4") (pintype "passive"))
    )
    (net (code "71") (name "unconnected-(T14-C{slash}-Pad4)") (class "Default")
      (node (ref "T14") (pin "4") (pinfunction "C/_4") (pintype "passive"))
    )
    (net (code "72") (name "unconnected-(X1-Pad20)") (class "Default")
      (node (ref "X1") (pin "20") (pinfunction "20_20") (pintype "passive"))
    )
  )
)
